# half_bridge.net
KiCad netlist of a schematic drawn in Altium Designer
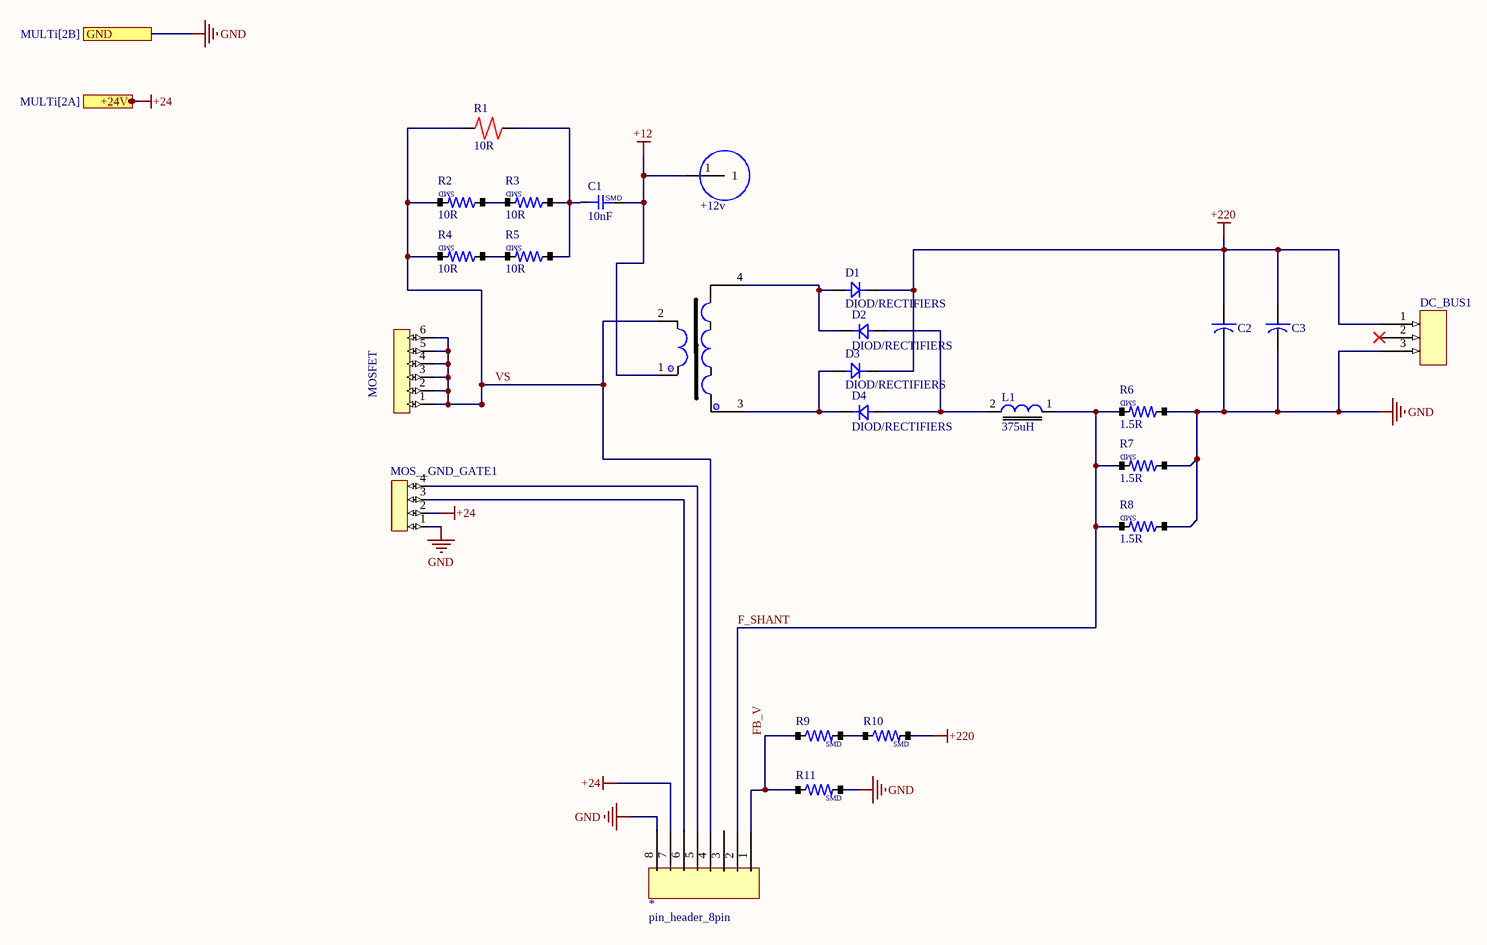
[diagram p0: half_bridge.SchDoc]

(export (version "E")
  (design (tool "Eeschema 10.0.6"))
  (components
    (comp (ref "*")
      (value "pin_header_8pin")
      (footprint "pin_header8")
      (libsource (lib "kave-eng-pro") (part "pin_header_8pin"))
    )
    (comp (ref "*1")
      (value "TRANS-FT8350C")
      (footprint "EI 3329D")
      (libsource (lib "kave-eng-pro") (part "TRANS-FT8350C"))
    )
    (comp (ref "+12v") (value "PIN1") (footprint "PIN1") (libsource (lib "kave-eng-pro") (part "PIN1")))
    (comp (ref "C1") (value "10nF") (footprint "CAP-1206") (libsource (lib "kave-eng-pro") (part "cap_smd")))
    (comp (ref "C2")
      (value "33uF")
      (footprint "CAP-EL_P5MM")
      (libsource (lib "kave-eng-pro") (part "cap-electrolit"))
    )
    (comp (ref "C3")
      (value "33uF")
      (footprint "CAP-EL_P5MM")
      (libsource (lib "kave-eng-pro") (part "cap-electrolit"))
    )
    (comp (ref "D1")
      (value "DIOD/RECTIFIERS")
      (footprint "1N4508_REZA")
      (libsource (lib "kave-eng-pro") (part "DIOD/RECTIFIERS"))
    )
    (comp (ref "D2")
      (value "DIOD/RECTIFIERS")
      (footprint "1N4508_REZA")
      (libsource (lib "kave-eng-pro") (part "DIOD/RECTIFIERS"))
    )
    (comp (ref "D3")
      (value "DIOD/RECTIFIERS")
      (footprint "1N4508_REZA")
      (libsource (lib "kave-eng-pro") (part "DIOD/RECTIFIERS"))
    )
    (comp (ref "D4")
      (value "DIOD/RECTIFIERS")
      (footprint "1N4508_REZA")
      (libsource (lib "kave-eng-pro") (part "DIOD/RECTIFIERS"))
    )
    (comp (ref "DC_BUS1")
      (value "~")
      (footprint "CONECTOR/FONIX/3PIN")
      (libsource (lib "kave-eng-pro") (part "CONECTOR/FONIX/3PIN"))
    )
    (comp (ref "L1")
      (value "375uH")
      (footprint "EI-28-SELF_DC")
      (libsource (lib "kave-eng-pro") (part "inductor"))
    )
    (comp (ref "MOSFET")
      (value "~")
      (footprint "pin_header_6pin")
      (libsource (lib "kave-eng-pro") (part "PIN_HEADER6"))
    )
    (comp (ref "MOS__GND_GATE1")
      (value "CONECTOR/XH/4PIN")
      (footprint "CONECTOR/XH/4PIN")
      (libsource (lib "kave-eng-pro") (part "CONECTOR/XH/4PIN"))
    )
    (comp (ref "R1")
      (value "10R")
      (footprint "RES/0.25W")
      (libsource (lib "kave-eng-pro") (part "RES/{lt}1W"))
    )
    (comp (ref "R2") (value "10R") (footprint "RES/1206") (libsource (lib "kave-eng-pro") (part "RES/SMD")))
    (comp (ref "R3") (value "10R") (footprint "RES/1206") (libsource (lib "kave-eng-pro") (part "RES/SMD")))
    (comp (ref "R4") (value "10R") (footprint "RES/1206") (libsource (lib "kave-eng-pro") (part "RES/SMD")))
    (comp (ref "R5") (value "10R") (footprint "RES/1206") (libsource (lib "kave-eng-pro") (part "RES/SMD")))
    (comp (ref "R6") (value "1.5R") (footprint "RES/1206") (libsource (lib "kave-eng-pro") (part "RES/SMD")))
    (comp (ref "R7") (value "1.5R") (footprint "RES/1206") (libsource (lib "kave-eng-pro") (part "RES/SMD")))
    (comp (ref "R8") (value "1.5R") (footprint "RES/1206") (libsource (lib "kave-eng-pro") (part "RES/SMD")))
    (comp (ref "R9") (value "r") (footprint "RES/1206") (libsource (lib "") (part "RES/SMD_1")))
    (comp (ref "R10") (value "r") (footprint "RES/1206") (libsource (lib "") (part "RES/SMD_1")))
    (comp (ref "R11") (value "r") (footprint "RES/1206") (libsource (lib "") (part "RES/SMD_1")))
  )
  (nets
    (net (code "1") (name "+12") (class "Default")
      (node (ref "*1") (pin "1") (pinfunction "0_1") (pintype "passive"))
      (node (ref "+12v") (pin "1") (pinfunction "1_1") (pintype "passive"))
      (node (ref "C1") (pin "2") (pintype "passive"))
    )
    (net (code "2") (name "+24") (class "Default")
      (node (ref "*") (pin "7") (pintype "open_collector"))
      (node (ref "MOS__GND_GATE1") (pin "2") (pintype "bidirectional"))
    )
    (net (code "3") (name "+220") (class "Default")
      (node (ref "C2") (pin "+") (pintype "passive"))
      (node (ref "C3") (pin "+") (pintype "passive"))
      (node (ref "D1") (pin "K") (pintype "passive"))
      (node (ref "D3") (pin "K") (pintype "passive"))
      (node (ref "DC_BUS1") (pin "1") (pintype "input"))
      (node (ref "R10") (pin "2") (pinfunction "2_2") (pintype "passive"))
    )
    (net (code "4") (name "/FB_V") (class "Default")
      (node (ref "*") (pin "1") (pintype "open_collector"))
      (node (ref "R11") (pin "1") (pinfunction "1_1") (pintype "passive"))
      (node (ref "R9") (pin "1") (pinfunction "1_1") (pintype "passive"))
    )
    (net (code "5") (name "/F_SHANT") (class "Default")
      (node (ref "*") (pin "2") (pintype "open_collector"))
      (node (ref "L1") (pin "1") (pintype "passive"))
      (node (ref "R6") (pin "2") (pinfunction "2_2") (pintype "passive"))
      (node (ref "R7") (pin "2") (pinfunction "2_2") (pintype "passive"))
      (node (ref "R8") (pin "2") (pinfunction "2_2") (pintype "passive"))
    )
    (net (code "6") (name "/VS") (class "Default")
      (node (ref "*") (pin "4") (pintype "open_collector"))
      (node (ref "*1") (pin "2") (pinfunction "0_2") (pintype "passive"))
      (node (ref "MOSFET") (pin "1") (pintype "bidirectional"))
      (node (ref "MOSFET") (pin "2") (pintype "bidirectional"))
      (node (ref "MOSFET") (pin "3") (pintype "bidirectional"))
      (node (ref "MOSFET") (pin "4") (pintype "bidirectional"))
      (node (ref "MOSFET") (pin "5") (pintype "bidirectional"))
      (node (ref "MOSFET") (pin "6") (pintype "bidirectional"))
      (node (ref "R1") (pin "1") (pintype "passive"))
      (node (ref "R2") (pin "2") (pinfunction "2_2") (pintype "passive"))
      (node (ref "R4") (pin "2") (pinfunction "2_2") (pintype "passive"))
    )
    (net (code "7") (name "GND") (class "Default")
      (node (ref "*") (pin "8") (pintype "open_collector"))
      (node (ref "C2") (pin "-") (pintype "passive"))
      (node (ref "C3") (pin "-") (pintype "passive"))
      (node (ref "DC_BUS1") (pin "3") (pintype "input"))
      (node (ref "MOS__GND_GATE1") (pin "1") (pintype "bidirectional"))
      (node (ref "R11") (pin "2") (pinfunction "2_2") (pintype "passive"))
      (node (ref "R6") (pin "1") (pinfunction "1_1") (pintype "passive"))
      (node (ref "R7") (pin "1") (pinfunction "1_1") (pintype "passive"))
      (node (ref "R8") (pin "1") (pinfunction "1_1") (pintype "passive"))
    )
    (net (code "8") (name "Net-(*-Pad5)") (class "Default")
      (node (ref "*") (pin "5") (pintype "open_collector"))
      (node (ref "MOS__GND_GATE1") (pin "4") (pintype "bidirectional"))
    )
    (net (code "9") (name "Net-(*-Pad6)") (class "Default")
      (node (ref "*") (pin "6") (pintype "open_collector"))
      (node (ref "MOS__GND_GATE1") (pin "3") (pintype "bidirectional"))
    )
    (net (code "10") (name "Net-(*1-0-Pad3)") (class "Default")
      (node (ref "*1") (pin "3") (pinfunction "0_3") (pintype "passive"))
      (node (ref "D3") (pin "A") (pintype "passive"))
      (node (ref "D4") (pin "K") (pintype "passive"))
    )
    (net (code "11") (name "Net-(*1-0-Pad4)") (class "Default")
      (node (ref "*1") (pin "4") (pinfunction "0_4") (pintype "passive"))
      (node (ref "D1") (pin "A") (pintype "passive"))
      (node (ref "D2") (pin "K") (pintype "passive"))
    )
    (net (code "12") (name "Net-(C1-Pad1)") (class "Default")
      (node (ref "C1") (pin "1") (pintype "passive"))
      (node (ref "R1") (pin "2") (pintype "passive"))
      (node (ref "R3") (pin "1") (pinfunction "1_1") (pintype "passive"))
      (node (ref "R5") (pin "1") (pinfunction "1_1") (pintype "passive"))
    )
    (net (code "13") (name "Net-(D2-PadA)") (class "Default")
      (node (ref "D2") (pin "A") (pintype "passive"))
      (node (ref "D4") (pin "A") (pintype "passive"))
      (node (ref "L1") (pin "2") (pintype "passive"))
    )
    (net (code "14") (name "Net-(R2-Pad1)") (class "Default")
      (node (ref "R2") (pin "1") (pinfunction "1_1") (pintype "passive"))
      (node (ref "R3") (pin "2") (pinfunction "2_2") (pintype "passive"))
    )
    (net (code "15") (name "Net-(R4-Pad1)") (class "Default")
      (node (ref "R4") (pin "1") (pinfunction "1_1") (pintype "passive"))
      (node (ref "R5") (pin "2") (pinfunction "2_2") (pintype "passive"))
    )
    (net (code "16") (name "Net-(R10-Pad1)") (class "Default")
      (node (ref "R10") (pin "1") (pinfunction "1_1") (pintype "passive"))
      (node (ref "R9") (pin "2") (pinfunction "2_2") (pintype "passive"))
    )
    (net (code "17") (name "unconnected-(*-Pad3)") (class "Default")
      (node (ref "*") (pin "3") (pintype "open_collector"))
    )
    (net (code "18") (name "unconnected-(DC_BUS1-Pad2)") (class "Default")
      (node (ref "DC_BUS1") (pin "2") (pintype "input+no_connect"))
    )
  )
)
